# data_interface.net
KiCad netlist of a schematic drawn in Altium Designer
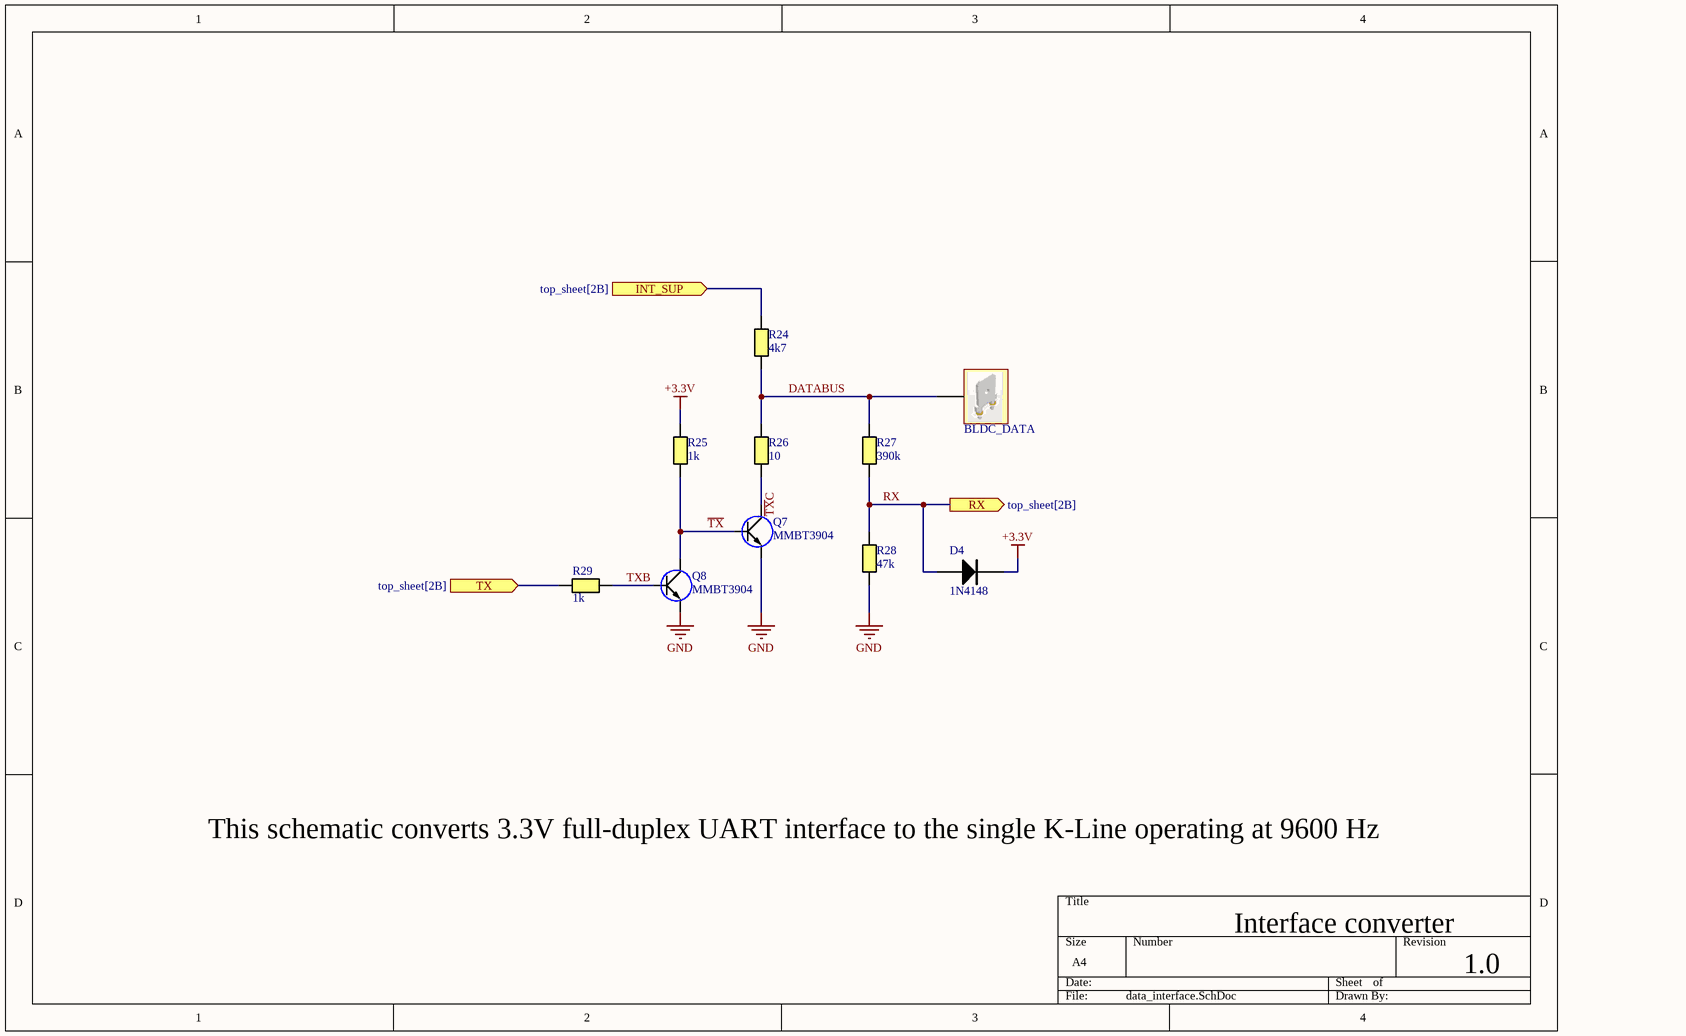
[diagram p0: data_interface.SchDoc]

(export (version "E")
  (design (tool "Eeschema 10.0.6"))
  (components
    (comp (ref "BLDC_DATA")
      (value "Crimp 6.3 single PCB")
      (footprint "Crimp 6.3mm single PCB")
      (description "Straight Mount Angle PCB Tab Terminal")
      (libsource (lib "Connectors") (part "Crimp 6.3 single PCB"))
    )
    (comp (ref "D4")
      (value "1N4148")
      (footprint "SOD80")
      (description "Small Signal Fast Switching Diodes")
      (libsource (lib "Diodes") (part "1N4148"))
    )
    (comp (ref "Q7")
      (value "MMBT3904")
      (footprint "SOT23")
      (description "NPN General Purpose Transistor")
      (libsource (lib "Transistors") (part "2N3904"))
    )
    (comp (ref "Q8")
      (value "MMBT3904")
      (footprint "SOT23")
      (description "NPN General Purpose Transistor")
      (libsource (lib "Transistors") (part "2N3904"))
    )
    (comp (ref "R24")
      (value "4k7")
      (footprint "RESC0603(1608)_N")
      (description "Resistor Medium Density")
      (libsource (lib "Discrete") (part "Resistor M"))
    )
    (comp (ref "R25")
      (value "1k")
      (footprint "RESC0603(1608)_N")
      (description "Resistor Medium Density")
      (libsource (lib "Discrete") (part "Resistor M"))
    )
    (comp (ref "R26")
      (value "10")
      (footprint "RESC0603(1608)_N")
      (description "Resistor Medium Density")
      (libsource (lib "Discrete") (part "Resistor M"))
    )
    (comp (ref "R27")
      (value "390k")
      (footprint "RESC0603(1608)_N")
      (description "Resistor Medium Density")
      (libsource (lib "Discrete") (part "Resistor M"))
    )
    (comp (ref "R28")
      (value "47k")
      (footprint "RESC0603(1608)_N")
      (description "Resistor Medium Density")
      (libsource (lib "Discrete") (part "Resistor M"))
    )
    (comp (ref "R29")
      (value "1k")
      (footprint "RESC0603(1608)_N")
      (description "Resistor Medium Density")
      (libsource (lib "") (part "Resistor M_1"))
    )
  )
  (nets
    (net (code "1") (name "+3.3V") (class "Default")
      (node (ref "D4") (pin "2") (pinfunction "K_2") (pintype "passive"))
      (node (ref "R25") (pin "2") (pinfunction "2_2") (pintype "passive"))
    )
    (net (code "2") (name "/DATABUS") (class "Default")
      (node (ref "BLDC_DATA") (pin "1") (pintype "passive"))
      (node (ref "R24") (pin "1") (pinfunction "1_1") (pintype "passive"))
      (node (ref "R26") (pin "2") (pinfunction "2_2") (pintype "passive"))
      (node (ref "R27") (pin "2") (pinfunction "2_2") (pintype "passive"))
    )
    (net (code "3") (name "/INT_SUP") (class "Default")
      (node (ref "R24") (pin "2") (pinfunction "2_2") (pintype "passive"))
    )
    (net (code "4") (name "/RX") (class "Default")
      (node (ref "D4") (pin "1") (pinfunction "A_1") (pintype "passive"))
      (node (ref "R27") (pin "1") (pinfunction "1_1") (pintype "passive"))
      (node (ref "R28") (pin "2") (pinfunction "2_2") (pintype "passive"))
    )
    (net (code "5") (name "/TX") (class "Default")
      (node (ref "R29") (pin "1") (pinfunction "1_1") (pintype "passive"))
    )
    (net (code "6") (name "/TXB") (class "Default")
      (node (ref "Q8") (pin "1") (pinfunction "B_1") (pintype "passive"))
      (node (ref "R29") (pin "2") (pinfunction "2_2") (pintype "passive"))
    )
    (net (code "7") (name "/~{TX}") (class "Default")
      (node (ref "Q7") (pin "1") (pinfunction "B_1") (pintype "passive"))
      (node (ref "Q8") (pin "3") (pinfunction "C_3") (pintype "passive"))
      (node (ref "R25") (pin "1") (pinfunction "1_1") (pintype "passive"))
    )
    (net (code "8") (name "/~{TX}C") (class "Default")
      (node (ref "Q7") (pin "3") (pinfunction "C_3") (pintype "passive"))
      (node (ref "R26") (pin "1") (pinfunction "1_1") (pintype "passive"))
    )
    (net (code "9") (name "GND") (class "Default")
      (node (ref "Q7") (pin "2") (pinfunction "E_2") (pintype "passive"))
      (node (ref "Q8") (pin "2") (pinfunction "E_2") (pintype "passive"))
      (node (ref "R28") (pin "1") (pinfunction "1_1") (pintype "passive"))
    )
  )
)
